# Main.net
KiCad netlist of a schematic drawn in Altium Designer
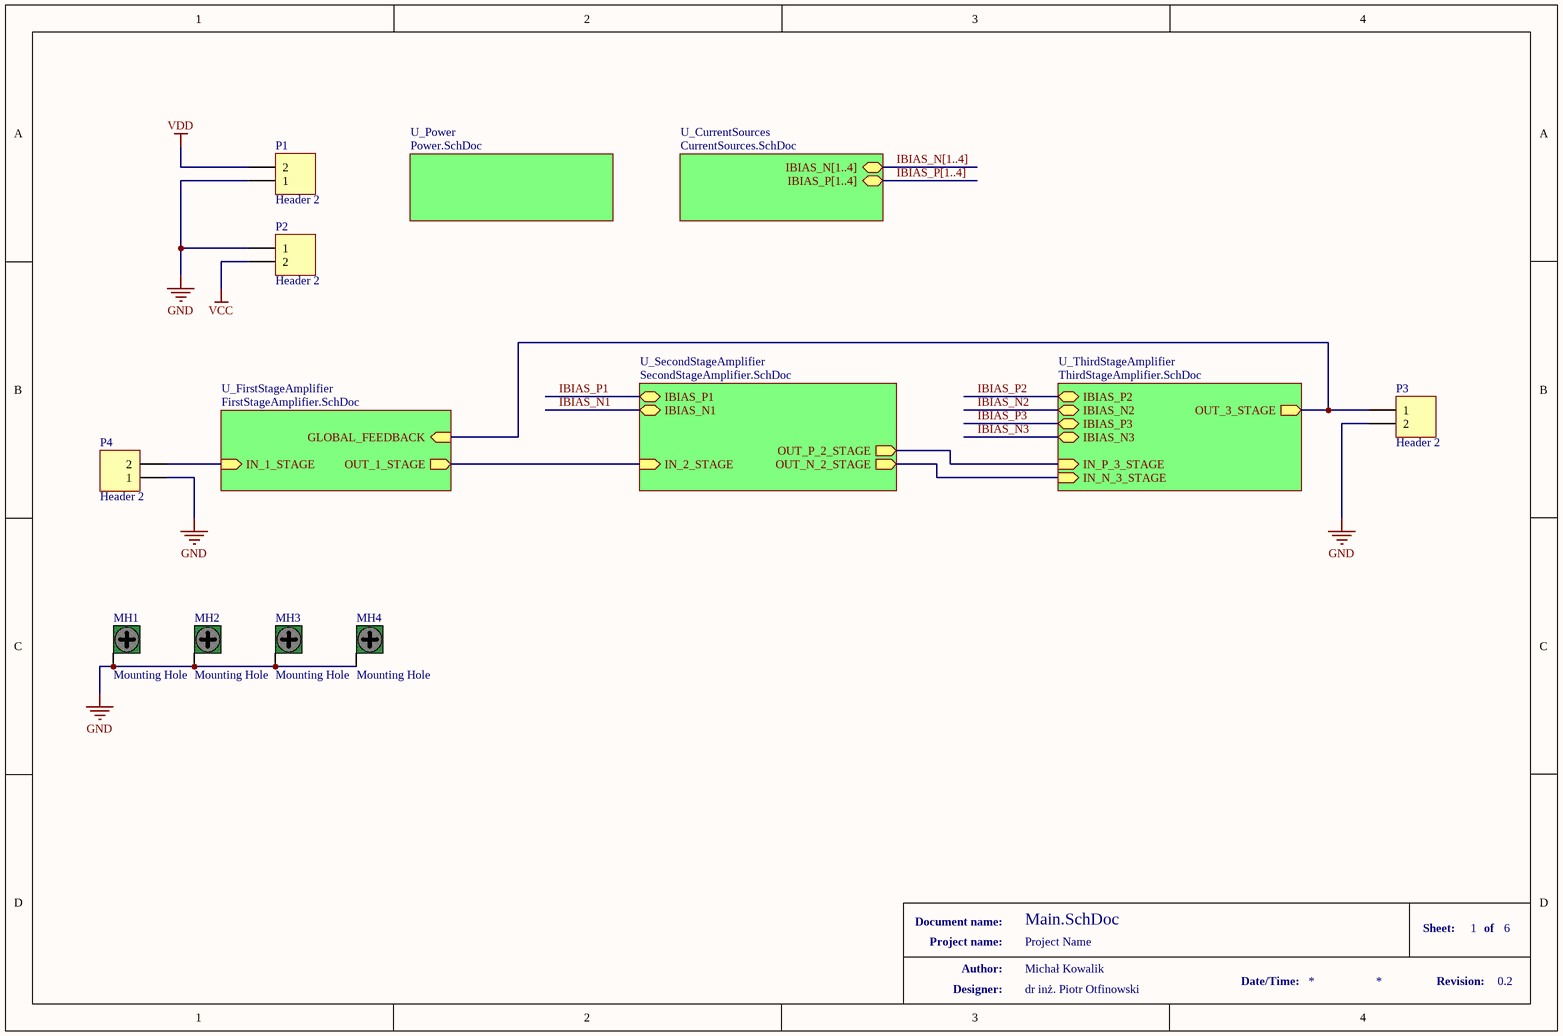
[diagram p0: Main.SchDoc]

(export (version "E")
  (design (tool "Eeschema 10.0.6"))
  (components
    (comp (ref "MH1")
      (value "Mounting Hole")
      (footprint "agh_racing_2018:MOUNTING HOLE 3mm")
      (libsource (lib "SchematicLib") (part "Mounting Hole"))
    )
    (comp (ref "MH2")
      (value "Mounting Hole")
      (footprint "agh_racing_2018:MOUNTING HOLE 3mm")
      (libsource (lib "SchematicLib") (part "Mounting Hole"))
    )
    (comp (ref "MH3")
      (value "Mounting Hole")
      (footprint "agh_racing_2018:MOUNTING HOLE 3mm")
      (libsource (lib "SchematicLib") (part "Mounting Hole"))
    )
    (comp (ref "MH4")
      (value "Mounting Hole")
      (footprint "agh_racing_2018:MOUNTING HOLE 3mm")
      (libsource (lib "SchematicLib") (part "Mounting Hole"))
    )
    (comp (ref "P1")
      (value "Header 2")
      (footprint "DG300-5.0-02P-13")
      (description "Header, 2-Pin")
      (fields (field (name "PUBLISHER") "Altium Limited"))
      (libsource (lib "SchematicLib") (part "Header 2"))
    )
    (comp (ref "P2")
      (value "Header 2")
      (footprint "DG300-5.0-02P-13")
      (description "Header, 2-Pin")
      (fields (field (name "PUBLISHER") "Altium Limited"))
      (libsource (lib "") (part "Header 2_1"))
    )
    (comp (ref "P3")
      (value "Header 2")
      (footprint "DG330-5.0-02P")
      (description "Header, 2-Pin")
      (fields (field (name "PUBLISHER") "Altium Limited"))
      (libsource (lib "") (part "Header 2_1"))
    )
    (comp (ref "P4")
      (value "Header 2")
      (footprint "DG300-5.0-02P-13")
      (description "Header, 2-Pin")
      (fields (field (name "PUBLISHER") "Altium Limited"))
      (libsource (lib "") (part "Header 2_2"))
    )
  )
  (nets
    (net (code "11") (name "/IN_1_STAGE") (class "Default")
      (node (ref "P4") (pin "2") (pinfunction "2_2") (pintype "passive"))
    )
    (net (code "13") (name "/OUT_3_STAGE") (class "Default")
      (node (ref "P3") (pin "1") (pinfunction "1_1") (pintype "passive"))
    )
    (net (code "16") (name "GND") (class "Default")
      (node (ref "MH1") (pin "MOUNTING") (pinfunction "MOUNTING_MOUNTING") (pintype "passive"))
      (node (ref "MH2") (pin "MOUNTING") (pinfunction "MOUNTING_MOUNTING") (pintype "passive"))
      (node (ref "MH3") (pin "MOUNTING") (pinfunction "MOUNTING_MOUNTING") (pintype "passive"))
      (node (ref "MH4") (pin "MOUNTING") (pinfunction "MOUNTING_MOUNTING") (pintype "passive"))
      (node (ref "P1") (pin "1") (pinfunction "1_1") (pintype "passive"))
      (node (ref "P2") (pin "1") (pinfunction "1_1") (pintype "passive"))
      (node (ref "P3") (pin "2") (pinfunction "2_2") (pintype "passive"))
      (node (ref "P4") (pin "1") (pinfunction "1_1") (pintype "passive"))
    )
    (net (code "17") (name "VCC") (class "Default")
      (node (ref "P2") (pin "2") (pinfunction "2_2") (pintype "passive"))
    )
    (net (code "18") (name "VDD") (class "Default")
      (node (ref "P1") (pin "2") (pinfunction "2_2") (pintype "passive"))
    )
  )
)
